# Sensores.net
KiCad netlist of a schematic drawn in Altium Designer
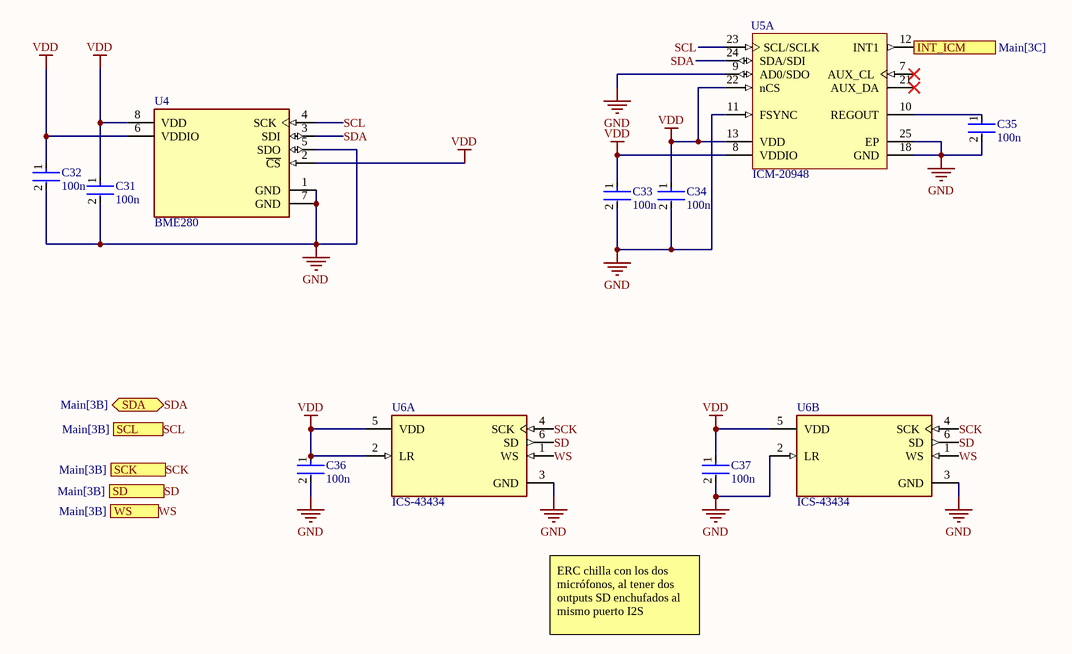
[diagram p0: Sensores.SchDoc]

(export (version "E")
  (design (tool "Eeschema 10.0.6"))
  (components
    (comp (ref "C31")
      (value "100n")
      (footprint "FP-GRM033-0_03-MFG")
      (description "Chip Multilayer Ceramic Capacitors for General Purpose, 0201, 0.10uF, X7S, 22%, 10%, 16V")
      (fields (field (name "TOLERANCE") "10%"))
      (libsource (lib "Altium Content Vault") (part "b4654b650e69147ec39a6b967a45e02"))
    )
    (comp (ref "C32")
      (value "100n")
      (footprint "FP-GRM033-0_03-MFG")
      (description "Chip Multilayer Ceramic Capacitors for General Purpose, 0201, 0.10uF, X7S, 22%, 10%, 16V")
      (fields (field (name "TOLERANCE") "10%"))
      (libsource (lib "Altium Content Vault") (part "b4654b650e69147ec39a6b967a45e02"))
    )
    (comp (ref "C33")
      (value "100n")
      (footprint "FP-GRM033-0_03-MFG")
      (description "Chip Multilayer Ceramic Capacitors for General Purpose, 0201, 0.10uF, X7S, 22%, 10%, 16V")
      (fields (field (name "TOLERANCE") "10%"))
      (libsource (lib "Altium Content Vault") (part "b4654b650e69147ec39a6b967a45e02"))
    )
    (comp (ref "C34")
      (value "100n")
      (footprint "FP-GRM033-0_03-MFG")
      (description "Chip Multilayer Ceramic Capacitors for General Purpose, 0201, 0.10uF, X7S, 22%, 10%, 16V")
      (fields (field (name "TOLERANCE") "10%"))
      (libsource (lib "Altium Content Vault") (part "b4654b650e69147ec39a6b967a45e02"))
    )
    (comp (ref "C35")
      (value "100n")
      (footprint "FP-GRM033-0_03-MFG")
      (description "Chip Multilayer Ceramic Capacitors for General Purpose, 0201, 0.10uF, X7S, 22%, 10%, 16V")
      (fields (field (name "TOLERANCE") "10%"))
      (libsource (lib "Altium Content Vault") (part "b4654b650e69147ec39a6b967a45e02"))
    )
    (comp (ref "C36")
      (value "100n")
      (footprint "FP-GRM033-0_03-MFG")
      (description "Chip Multilayer Ceramic Capacitors for General Purpose, 0201, 0.10uF, X7S, 22%, 10%, 16V")
      (fields (field (name "TOLERANCE") "10%"))
      (libsource (lib "Altium Content Vault") (part "b4654b650e69147ec39a6b967a45e02"))
    )
    (comp (ref "C37")
      (value "100n")
      (footprint "FP-GRM033-0_03-MFG")
      (description "Chip Multilayer Ceramic Capacitors for General Purpose, 0201, 0.10uF, X7S, 22%, 10%, 16V")
      (fields (field (name "TOLERANCE") "10%"))
      (libsource (lib "Altium Content Vault") (part "b4654b650e69147ec39a6b967a45e02"))
    )
    (comp (ref "U4")
      (value "BME280")
      (footprint "FP-BME280-MFG")
      (description "SENSOR PRESSURE HUMIDITY TEMP")
      (libsource (lib "Altium Content Vault") (part "d58e2f6669bc67e6a2bc6a28610ca79"))
    )
    (comp (ref "U5")
      (value "ICM-20948")
      (footprint "TDK-QFN-24_L")
      (fields (field (name "MANUFACTURER") "TDK"))
      (libsource (lib "Altium Content Vault") (part "TDK-ICM-20948-QFN-24"))
    )
    (comp (ref "U6A")
      (value "ICS-43434")
      (footprint "FP-ICS-43434-MFG")
      (description "ICS-43434 Mic Omni-Directional -26dB 3.63V Rectangular Solder Pad T/R")
      (libsource (lib "Altium Content Vault") (part "ae05e933d23a1a1b08b70095a55dc98"))
    )
    (comp (ref "U6B")
      (value "ICS-43434")
      (footprint "FP-ICS-43434-MFG")
      (description "ICS-43434 Mic Omni-Directional -26dB 3.63V Rectangular Solder Pad T/R")
      (libsource (lib "Altium Content Vault") (part "ae05e933d23a1a1b08b70095a55dc98"))
    )
  )
  (nets
    (net (code "1") (name "/INT_ICM") (class "Default")
      (node (ref "U5") (pin "12") (pinfunction "INT1_12") (pintype "output"))
    )
    (net (code "2") (name "/SCK") (class "Default")
      (node (ref "U6A") (pin "4") (pinfunction "SCK_4") (pintype "input"))
      (node (ref "U6B") (pin "4") (pinfunction "SCK_4") (pintype "input"))
    )
    (net (code "3") (name "/SCL") (class "Default")
      (node (ref "U4") (pin "4") (pinfunction "SCK_4") (pintype "input"))
      (node (ref "U5") (pin "23") (pinfunction "SCL/SCLK_23") (pintype "input"))
    )
    (net (code "4") (name "/SD") (class "Default")
      (node (ref "U6A") (pin "6") (pinfunction "SD_6") (pintype "output"))
      (node (ref "U6B") (pin "6") (pinfunction "SD_6") (pintype "output"))
    )
    (net (code "5") (name "/SDA") (class "Default")
      (node (ref "U4") (pin "3") (pinfunction "SDI_3") (pintype "bidirectional"))
      (node (ref "U5") (pin "24") (pinfunction "SDA/SDI_24") (pintype "bidirectional"))
    )
    (net (code "6") (name "/WS") (class "Default")
      (node (ref "U6A") (pin "1") (pinfunction "WS_1") (pintype "input"))
      (node (ref "U6B") (pin "1") (pinfunction "WS_1") (pintype "input"))
    )
    (net (code "7") (name "GND") (class "Default")
      (node (ref "C31") (pin "2") (pinfunction "2_2") (pintype "passive"))
      (node (ref "C32") (pin "2") (pinfunction "2_2") (pintype "passive"))
      (node (ref "C33") (pin "2") (pinfunction "2_2") (pintype "passive"))
      (node (ref "C34") (pin "2") (pinfunction "2_2") (pintype "passive"))
      (node (ref "C35") (pin "2") (pinfunction "2_2") (pintype "passive"))
      (node (ref "C36") (pin "2") (pinfunction "2_2") (pintype "passive"))
      (node (ref "C37") (pin "2") (pinfunction "2_2") (pintype "passive"))
      (node (ref "U4") (pin "1") (pinfunction "GND_1") (pintype "power_in"))
      (node (ref "U4") (pin "5") (pinfunction "SDO_5") (pintype "bidirectional"))
      (node (ref "U4") (pin "7") (pinfunction "GND_7") (pintype "power_in"))
      (node (ref "U5") (pin "11") (pinfunction "FSYNC_11") (pintype "input"))
      (node (ref "U5") (pin "18") (pinfunction "GND_18") (pintype "power_in"))
      (node (ref "U5") (pin "25") (pinfunction "EP_25") (pintype "passive"))
      (node (ref "U5") (pin "9") (pinfunction "AD0/SDO_9") (pintype "bidirectional"))
      (node (ref "U6A") (pin "3") (pinfunction "GND_3") (pintype "power_in"))
      (node (ref "U6B") (pin "2") (pinfunction "LR_2") (pintype "input"))
      (node (ref "U6B") (pin "3") (pinfunction "GND_3") (pintype "power_in"))
    )
    (net (code "8") (name "Net-(U5A-REGOUT)") (class "Default")
      (node (ref "C35") (pin "1") (pinfunction "1_1") (pintype "passive"))
      (node (ref "U5") (pin "10") (pinfunction "REGOUT_10") (pintype "passive"))
    )
    (net (code "9") (name "VDD") (class "Default")
      (node (ref "C31") (pin "1") (pinfunction "1_1") (pintype "passive"))
      (node (ref "C32") (pin "1") (pinfunction "1_1") (pintype "passive"))
      (node (ref "C33") (pin "1") (pinfunction "1_1") (pintype "passive"))
      (node (ref "C34") (pin "1") (pinfunction "1_1") (pintype "passive"))
      (node (ref "C36") (pin "1") (pinfunction "1_1") (pintype "passive"))
      (node (ref "C37") (pin "1") (pinfunction "1_1") (pintype "passive"))
      (node (ref "U4") (pin "2") (pinfunction "~{CS}_2") (pintype "input"))
      (node (ref "U4") (pin "6") (pinfunction "VDDIO_6") (pintype "power_in"))
      (node (ref "U4") (pin "8") (pinfunction "VDD_8") (pintype "power_in"))
      (node (ref "U5") (pin "13") (pinfunction "VDD_13") (pintype "power_in"))
      (node (ref "U5") (pin "22") (pinfunction "nCS_22") (pintype "input"))
      (node (ref "U5") (pin "8") (pinfunction "VDDIO_8") (pintype "power_in"))
      (node (ref "U6A") (pin "2") (pinfunction "LR_2") (pintype "input"))
      (node (ref "U6A") (pin "5") (pinfunction "VDD_5") (pintype "power_in"))
      (node (ref "U6B") (pin "5") (pinfunction "VDD_5") (pintype "power_in"))
    )
    (net (code "10") (name "unconnected-(U5A-AUX_CL-Pad7)") (class "Default")
      (node (ref "U5") (pin "7") (pinfunction "AUX_CL_7") (pintype "input+no_connect"))
    )
    (net (code "11") (name "unconnected-(U5A-AUX_DA-Pad21)") (class "Default")
      (node (ref "U5") (pin "21") (pinfunction "AUX_DA_21") (pintype "passive+no_connect"))
    )
  )
)
